# EBR01.net
KiCad netlist of a schematic drawn in EAGLE
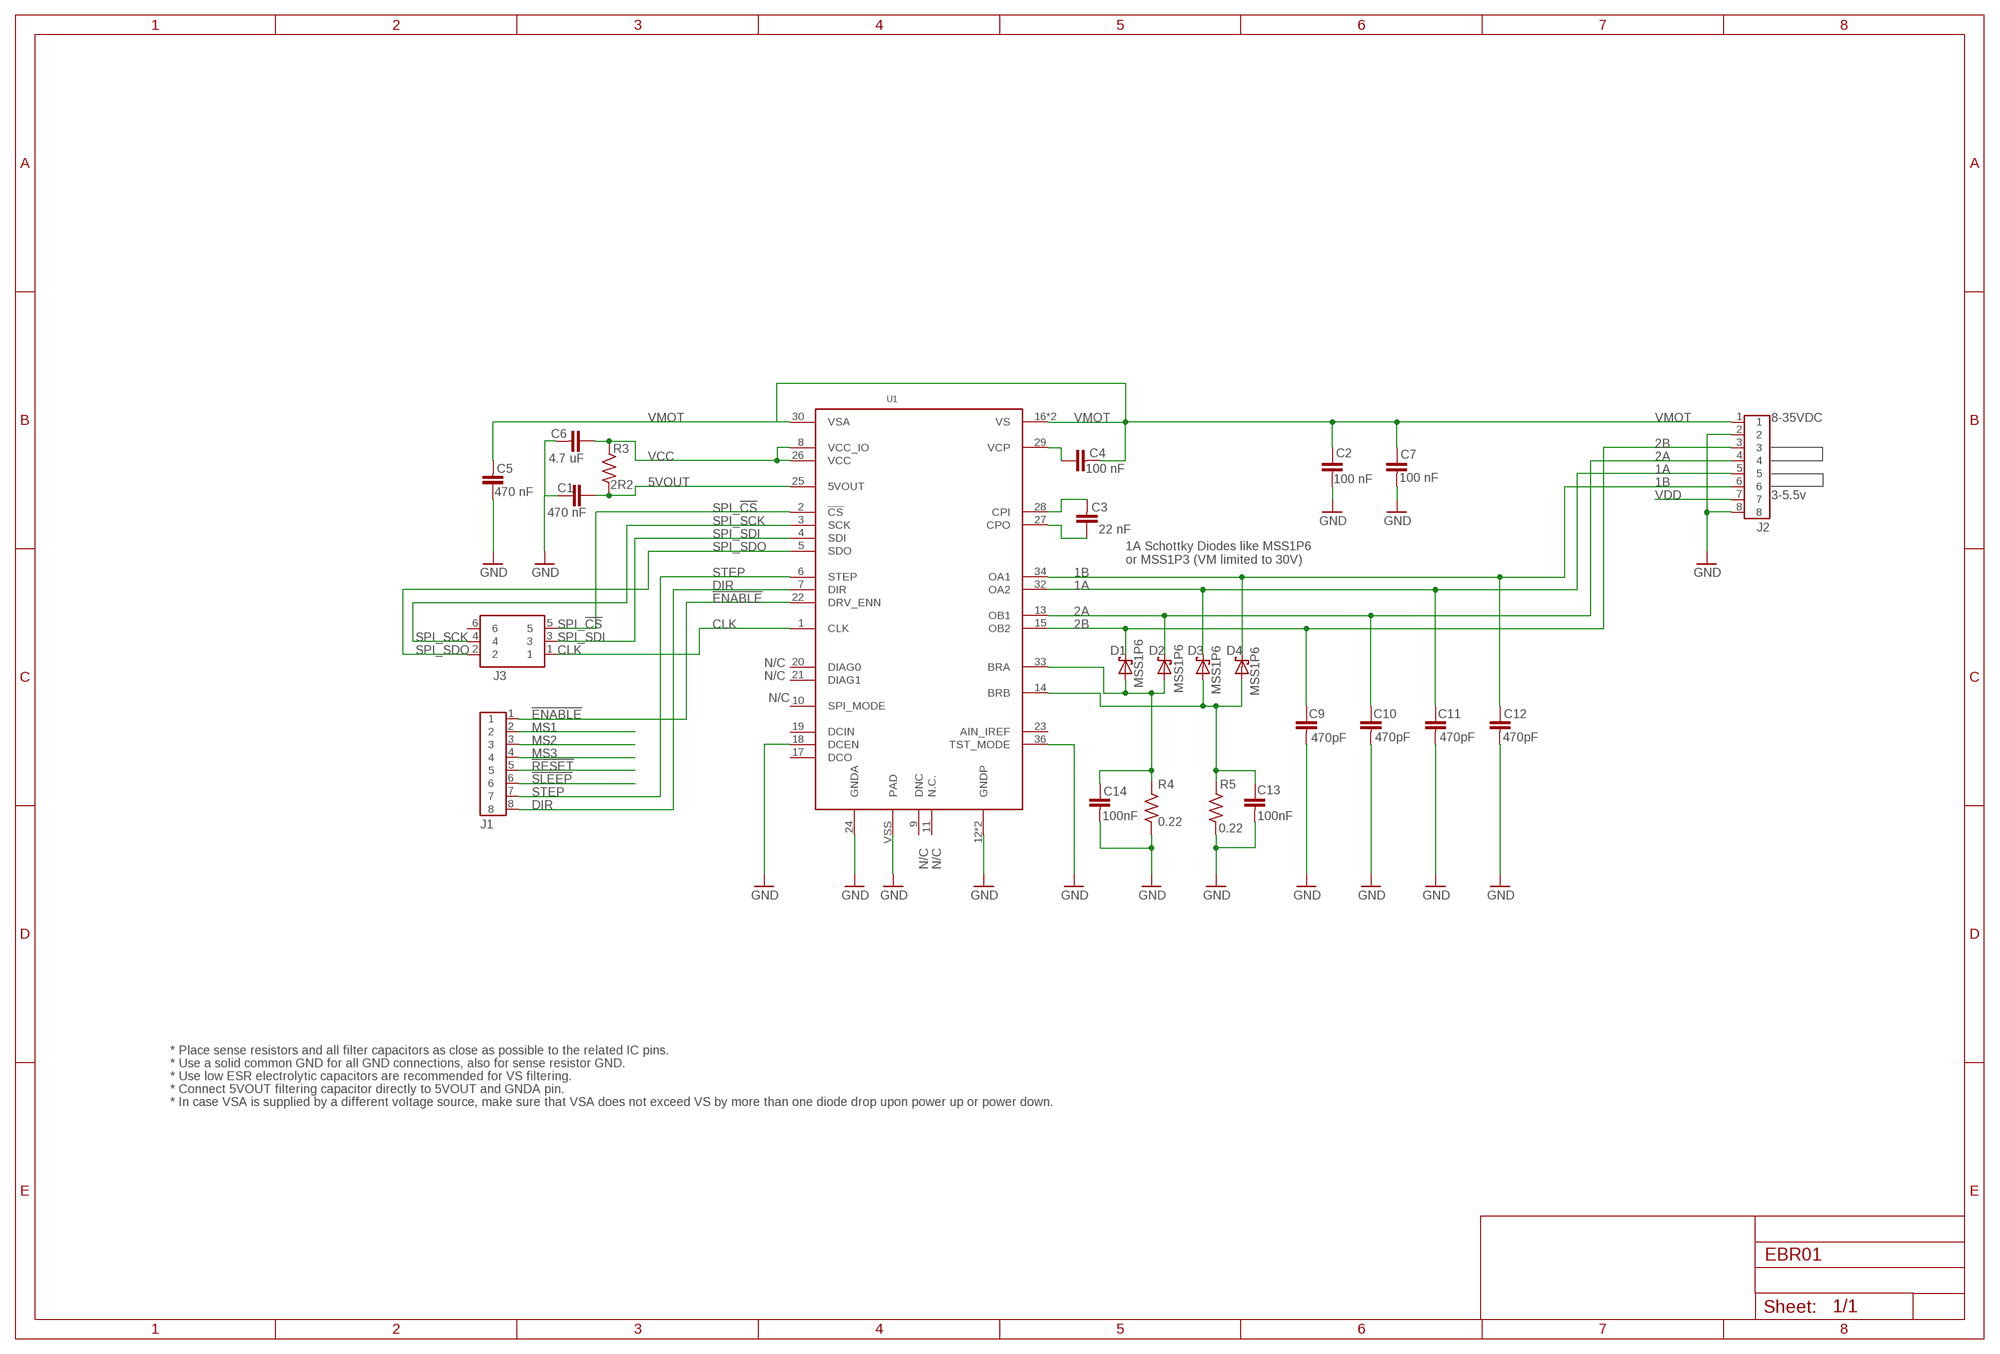
[diagram p0: schematic, sheet 1]

(export (version "E")
  (design (tool "Eeschema 10.0.6"))
  (components
    (comp (ref "C1")
      (value "470 nF")
      (footprint "eagle-import:0603-CAP")
      (libsource (lib "eagle-import") (part "CAP0603-CAP"))
    )
    (comp (ref "C2")
      (value "100 nF")
      (footprint "eagle-import:C0603")
      (libsource (lib "eagle-import") (part "CPL-CAP-X7R-0603-100NF-50V"))
    )
    (comp (ref "C3")
      (value "22 nF")
      (footprint "eagle-import:C0603")
      (libsource (lib "eagle-import") (part "CPL-CAP-X7R-0603-22NF-50VKEMETC0603C223K5RAC"))
    )
    (comp (ref "C4")
      (value "100 nF")
      (footprint "eagle-import:C0603")
      (libsource (lib "eagle-import") (part "CPL-CAP-X7R-0603-100NF-50V"))
    )
    (comp (ref "C5")
      (value "470 nF")
      (footprint "eagle-import:C0603")
      (libsource (lib "eagle-import") (part "CPL-CAP-X7R-0603-470NF-16V"))
    )
    (comp (ref "C6")
      (value "4.7 uF")
      (footprint "eagle-import:C0603")
      (libsource (lib "eagle-import") (part "CPL-CAP-X5R-4.7UF-10V"))
    )
    (comp (ref "C7")
      (value "100 nF")
      (footprint "eagle-import:C0603")
      (libsource (lib "eagle-import") (part "CPL-CAP-X7R-0603-100NF-50V"))
    )
    (comp (ref "C9")
      (value "470pF")
      (footprint "eagle-import:C0603")
      (libsource (lib "eagle-import") (part "CPL-CAP-X7R-0603-470PF-100V"))
    )
    (comp (ref "C10")
      (value "470pF")
      (footprint "eagle-import:C0603")
      (libsource (lib "eagle-import") (part "CPL-CAP-X7R-0603-470PF-100V"))
    )
    (comp (ref "C11")
      (value "470pF")
      (footprint "eagle-import:C0603")
      (libsource (lib "eagle-import") (part "CPL-CAP-X7R-0603-470PF-100V"))
    )
    (comp (ref "C12")
      (value "470pF")
      (footprint "eagle-import:C0603")
      (libsource (lib "eagle-import") (part "CPL-CAP-X7R-0603-470PF-100V"))
    )
    (comp (ref "C13")
      (value "100nF")
      (footprint "eagle-import:C0603")
      (libsource (lib "eagle-import") (part "CPL-CAP-X7R-0603-100NF-50V"))
    )
    (comp (ref "C14")
      (value "100nF")
      (footprint "eagle-import:C0603")
      (libsource (lib "eagle-import") (part "CPL-CAP-X7R-0603-100NF-50V"))
    )
    (comp (ref "D1")
      (value "MSS1P6")
      (footprint "eagle-import:MICRO-SMP")
      (libsource (lib "eagle-import") (part "CPL-DIO-MSS1P6-MICROSMP"))
    )
    (comp (ref "D2")
      (value "MSS1P6")
      (footprint "eagle-import:MICRO-SMP")
      (libsource (lib "eagle-import") (part "CPL-DIO-MSS1P6-MICROSMP"))
    )
    (comp (ref "D3")
      (value "MSS1P6")
      (footprint "eagle-import:MICRO-SMP")
      (libsource (lib "eagle-import") (part "CPL-DIO-MSS1P6-MICROSMP"))
    )
    (comp (ref "D4")
      (value "MSS1P6")
      (footprint "eagle-import:MICRO-SMP")
      (libsource (lib "eagle-import") (part "CPL-DIO-MSS1P6-MICROSMP"))
    )
    (comp (ref "J1")
      (value "CPL-CON-HEADER-0.1IN-8P-M")
      (footprint "eagle-import:CON-HDR-8POS-MALE")
      (libsource (lib "eagle-import") (part "CPL-CON-HEADER-0.1IN-8P-M"))
    )
    (comp (ref "J2")
      (value "CPL-CON-HEADER-0.1IN-8P-M")
      (footprint "eagle-import:CON-HDR-8POS-MALE")
      (libsource (lib "eagle-import") (part "CPL-CON-HEADER-0.1IN-8P-M"))
    )
    (comp (ref "J3")
      (value "CPL-CON-HEADER-0.1IN-2X3P-M")
      (footprint "eagle-import:CON-HDR-2X3P")
      (libsource (lib "eagle-import") (part "CPL-CON-HEADER-0.1IN-2X3P-M"))
    )
    (comp (ref "R3")
      (value "2R2")
      (footprint "eagle-import:R0603")
      (libsource (lib "eagle-import") (part "CPL-RES-0603-2.2-0.25W"))
    )
    (comp (ref "R4")
      (value "0.22")
      (footprint "eagle-import:R1206")
      (libsource (lib "eagle-import") (part "CPL-RES-1206-0.22-0.5W"))
    )
    (comp (ref "R5")
      (value "0.22")
      (footprint "eagle-import:R1206")
      (libsource (lib "eagle-import") (part "CPL-RES-1206-0.22-0.5W"))
    )
    (comp (ref "U1")
      (value "CPL-MDR-2PHSTEPPER")
      (footprint "eagle-import:QFN36-(5X6)")
      (libsource (lib "eagle-import") (part "CPL-MDR-2PHSTEPPER"))
    )
  )
  (nets
    (net (code "1") (name "/1A") (class "Default")
      (node (ref "C11") (pin "1") (pinfunction "1_1") (pintype "passive"))
      (node (ref "D3") (pin "NEG") (pinfunction "C_NEG") (pintype "passive"))
      (node (ref "J2") (pin "5") (pinfunction "5_5") (pintype "passive"))
      (node (ref "U1") (pin "32") (pinfunction "OA2_32") (pintype "bidirectional"))
    )
    (net (code "2") (name "/1B") (class "Default")
      (node (ref "C12") (pin "1") (pinfunction "1_1") (pintype "passive"))
      (node (ref "D4") (pin "NEG") (pinfunction "C_NEG") (pintype "passive"))
      (node (ref "J2") (pin "6") (pinfunction "6_6") (pintype "passive"))
      (node (ref "U1") (pin "34") (pinfunction "OA1_34") (pintype "bidirectional"))
    )
    (net (code "3") (name "/2A") (class "Default")
      (node (ref "C10") (pin "1") (pinfunction "1_1") (pintype "passive"))
      (node (ref "D2") (pin "NEG") (pinfunction "C_NEG") (pintype "passive"))
      (node (ref "J2") (pin "4") (pinfunction "4_4") (pintype "passive"))
      (node (ref "U1") (pin "13") (pinfunction "OB1_13") (pintype "bidirectional"))
    )
    (net (code "4") (name "/2B") (class "Default")
      (node (ref "C9") (pin "1") (pinfunction "1_1") (pintype "passive"))
      (node (ref "D1") (pin "NEG") (pinfunction "C_NEG") (pintype "passive"))
      (node (ref "J2") (pin "3") (pinfunction "3_3") (pintype "passive"))
      (node (ref "U1") (pin "15") (pinfunction "OB2_15") (pintype "bidirectional"))
    )
    (net (code "5") (name "/5VOUT") (class "Default")
      (node (ref "C1") (pin "1") (pinfunction "1_1") (pintype "passive"))
      (node (ref "R3") (pin "1") (pinfunction "1_1") (pintype "passive"))
      (node (ref "U1") (pin "25") (pinfunction "5VOUT_25") (pintype "bidirectional"))
    )
    (net (code "6") (name "/CLK") (class "Default")
      (node (ref "J3") (pin "1") (pinfunction "1_1") (pintype "passive"))
      (node (ref "U1") (pin "1") (pinfunction "CLK_1") (pintype "bidirectional"))
    )
    (net (code "7") (name "/DIR") (class "Default")
      (node (ref "J1") (pin "8") (pinfunction "8_8") (pintype "passive"))
      (node (ref "U1") (pin "7") (pinfunction "DIR_7") (pintype "bidirectional"))
    )
    (net (code "8") (name "/MS1") (class "Default")
      (node (ref "J1") (pin "2") (pinfunction "2_2") (pintype "passive"))
    )
    (net (code "9") (name "/MS2") (class "Default")
      (node (ref "J1") (pin "3") (pinfunction "3_3") (pintype "passive"))
    )
    (net (code "10") (name "/MS3") (class "Default")
      (node (ref "J1") (pin "4") (pinfunction "4_4") (pintype "passive"))
    )
    (net (code "11") (name "/SPI_SCK") (class "Default")
      (node (ref "J3") (pin "4") (pinfunction "4_4") (pintype "passive"))
      (node (ref "U1") (pin "3") (pinfunction "SCK_3") (pintype "bidirectional"))
    )
    (net (code "12") (name "/SPI_SDI") (class "Default")
      (node (ref "J3") (pin "3") (pinfunction "3_3") (pintype "passive"))
      (node (ref "U1") (pin "4") (pinfunction "SDI_4") (pintype "bidirectional"))
    )
    (net (code "13") (name "/SPI_SDO") (class "Default")
      (node (ref "J3") (pin "2") (pinfunction "2_2") (pintype "passive"))
      (node (ref "U1") (pin "5") (pinfunction "SDO_5") (pintype "bidirectional"))
    )
    (net (code "14") (name "/SPI_~{CS}") (class "Default")
      (node (ref "J3") (pin "5") (pinfunction "5_5") (pintype "passive"))
      (node (ref "U1") (pin "2") (pinfunction "~{CS}_2") (pintype "bidirectional"))
    )
    (net (code "15") (name "/STEP") (class "Default")
      (node (ref "J1") (pin "7") (pinfunction "7_7") (pintype "passive"))
      (node (ref "U1") (pin "6") (pinfunction "STEP_6") (pintype "bidirectional"))
    )
    (net (code "16") (name "/VCC") (class "Default")
      (node (ref "C6") (pin "1") (pinfunction "1_1") (pintype "passive"))
      (node (ref "R3") (pin "2") (pinfunction "2_2") (pintype "passive"))
      (node (ref "U1") (pin "26") (pinfunction "VCC_26") (pintype "bidirectional"))
      (node (ref "U1") (pin "8") (pinfunction "VCC_IO_8") (pintype "bidirectional"))
    )
    (net (code "17") (name "/VDD") (class "Default")
      (node (ref "J2") (pin "7") (pinfunction "7_7") (pintype "passive"))
    )
    (net (code "18") (name "/VMOT") (class "Default")
      (node (ref "C2") (pin "1") (pinfunction "1_1") (pintype "passive"))
      (node (ref "C4") (pin "2") (pinfunction "2_2") (pintype "passive"))
      (node (ref "C5") (pin "2") (pinfunction "2_2") (pintype "passive"))
      (node (ref "C7") (pin "1") (pinfunction "1_1") (pintype "passive"))
      (node (ref "J2") (pin "1") (pinfunction "1_1") (pintype "passive"))
      (node (ref "U1") (pin "16") (pinfunction "VS_16") (pintype "bidirectional"))
      (node (ref "U1") (pin "30") (pinfunction "VSA_30") (pintype "bidirectional"))
      (node (ref "U1") (pin "31") (pinfunction "VS_31") (pintype "bidirectional"))
    )
    (net (code "19") (name "/~{ENABLE}") (class "Default")
      (node (ref "J1") (pin "1") (pinfunction "1_1") (pintype "passive"))
      (node (ref "U1") (pin "22") (pinfunction "DRV_ENN_22") (pintype "bidirectional"))
    )
    (net (code "20") (name "/~{RESET}") (class "Default")
      (node (ref "J1") (pin "5") (pinfunction "5_5") (pintype "passive"))
    )
    (net (code "21") (name "/~{SLEEP}") (class "Default")
      (node (ref "J1") (pin "6") (pinfunction "6_6") (pintype "passive"))
    )
    (net (code "22") (name "GND") (class "Default")
      (node (ref "C1") (pin "2") (pinfunction "2_2") (pintype "passive"))
      (node (ref "C10") (pin "2") (pinfunction "2_2") (pintype "passive"))
      (node (ref "C11") (pin "2") (pinfunction "2_2") (pintype "passive"))
      (node (ref "C12") (pin "2") (pinfunction "2_2") (pintype "passive"))
      (node (ref "C13") (pin "2") (pinfunction "2_2") (pintype "passive"))
      (node (ref "C14") (pin "2") (pinfunction "2_2") (pintype "passive"))
      (node (ref "C2") (pin "2") (pinfunction "2_2") (pintype "passive"))
      (node (ref "C5") (pin "1") (pinfunction "1_1") (pintype "passive"))
      (node (ref "C6") (pin "2") (pinfunction "2_2") (pintype "passive"))
      (node (ref "C7") (pin "2") (pinfunction "2_2") (pintype "passive"))
      (node (ref "C9") (pin "2") (pinfunction "2_2") (pintype "passive"))
      (node (ref "J2") (pin "2") (pinfunction "2_2") (pintype "passive"))
      (node (ref "J2") (pin "8") (pinfunction "8_8") (pintype "passive"))
      (node (ref "R4") (pin "1") (pinfunction "1_1") (pintype "passive"))
      (node (ref "R5") (pin "1") (pinfunction "1_1") (pintype "passive"))
      (node (ref "U1") (pin "12") (pinfunction "GNDP_12") (pintype "bidirectional"))
      (node (ref "U1") (pin "18") (pinfunction "DCEN_18") (pintype "bidirectional"))
      (node (ref "U1") (pin "24") (pinfunction "GNDA_24") (pintype "bidirectional"))
      (node (ref "U1") (pin "35") (pinfunction "GNDP_35") (pintype "bidirectional"))
      (node (ref "U1") (pin "36") (pinfunction "TST_MODE_36") (pintype "bidirectional"))
      (node (ref "U1") (pin "VSS") (pinfunction "PAD_VSS") (pintype "bidirectional"))
    )
    (net (code "23") (name "Net-(D1-A)") (class "Default")
      (node (ref "C14") (pin "1") (pinfunction "1_1") (pintype "passive"))
      (node (ref "D1") (pin "POS") (pinfunction "A_POS") (pintype "passive"))
      (node (ref "D2") (pin "POS") (pinfunction "A_POS") (pintype "passive"))
      (node (ref "R4") (pin "2") (pinfunction "2_2") (pintype "passive"))
      (node (ref "U1") (pin "33") (pinfunction "BRA_33") (pintype "bidirectional"))
    )
    (net (code "24") (name "Net-(D3-A)") (class "Default")
      (node (ref "C13") (pin "1") (pinfunction "1_1") (pintype "passive"))
      (node (ref "D3") (pin "POS") (pinfunction "A_POS") (pintype "passive"))
      (node (ref "D4") (pin "POS") (pinfunction "A_POS") (pintype "passive"))
      (node (ref "R5") (pin "2") (pinfunction "2_2") (pintype "passive"))
      (node (ref "U1") (pin "14") (pinfunction "BRB_14") (pintype "bidirectional"))
    )
    (net (code "25") (name "Net-(U1-CPI)") (class "Default")
      (node (ref "C3") (pin "2") (pinfunction "2_2") (pintype "passive"))
      (node (ref "U1") (pin "28") (pinfunction "CPI_28") (pintype "bidirectional"))
    )
    (net (code "26") (name "Net-(U1-CPO)") (class "Default")
      (node (ref "C3") (pin "1") (pinfunction "1_1") (pintype "passive"))
      (node (ref "U1") (pin "27") (pinfunction "CPO_27") (pintype "bidirectional"))
    )
    (net (code "27") (name "Net-(U1-VCP)") (class "Default")
      (node (ref "C4") (pin "1") (pinfunction "1_1") (pintype "passive"))
      (node (ref "U1") (pin "29") (pinfunction "VCP_29") (pintype "bidirectional"))
    )
    (net (code "28") (name "unconnected-(J3-Pad6)") (class "Default")
      (node (ref "J3") (pin "6") (pinfunction "6_6") (pintype "passive"))
    )
    (net (code "29") (name "unconnected-(U1-AIN_IREF-Pad23)") (class "Default")
      (node (ref "U1") (pin "23") (pinfunction "AIN_IREF_23") (pintype "bidirectional"))
    )
    (net (code "30") (name "unconnected-(U1-DCIN-Pad19)") (class "Default")
      (node (ref "U1") (pin "19") (pinfunction "DCIN_19") (pintype "bidirectional"))
    )
    (net (code "31") (name "unconnected-(U1-DCO-Pad17)") (class "Default")
      (node (ref "U1") (pin "17") (pinfunction "DCO_17") (pintype "bidirectional"))
    )
    (net (code "32") (name "unconnected-(U1-DIAG0-Pad20)") (class "Default")
      (node (ref "U1") (pin "20") (pinfunction "DIAG0_20") (pintype "bidirectional"))
    )
    (net (code "33") (name "unconnected-(U1-DIAG1-Pad21)") (class "Default")
      (node (ref "U1") (pin "21") (pinfunction "DIAG1_21") (pintype "bidirectional"))
    )
    (net (code "34") (name "unconnected-(U1-DNC-Pad9)") (class "Default")
      (node (ref "U1") (pin "9") (pinfunction "DNC_9") (pintype "bidirectional"))
    )
    (net (code "35") (name "unconnected-(U1-N.C.-Pad11)") (class "Default")
      (node (ref "U1") (pin "11") (pinfunction "N.C._11") (pintype "bidirectional"))
    )
    (net (code "36") (name "unconnected-(U1-SPI_MODE-Pad10)") (class "Default")
      (node (ref "U1") (pin "10") (pinfunction "SPI_MODE_10") (pintype "bidirectional"))
    )
  )
)
